# Hardware.net
KiCad netlist of a schematic drawn in EAGLE
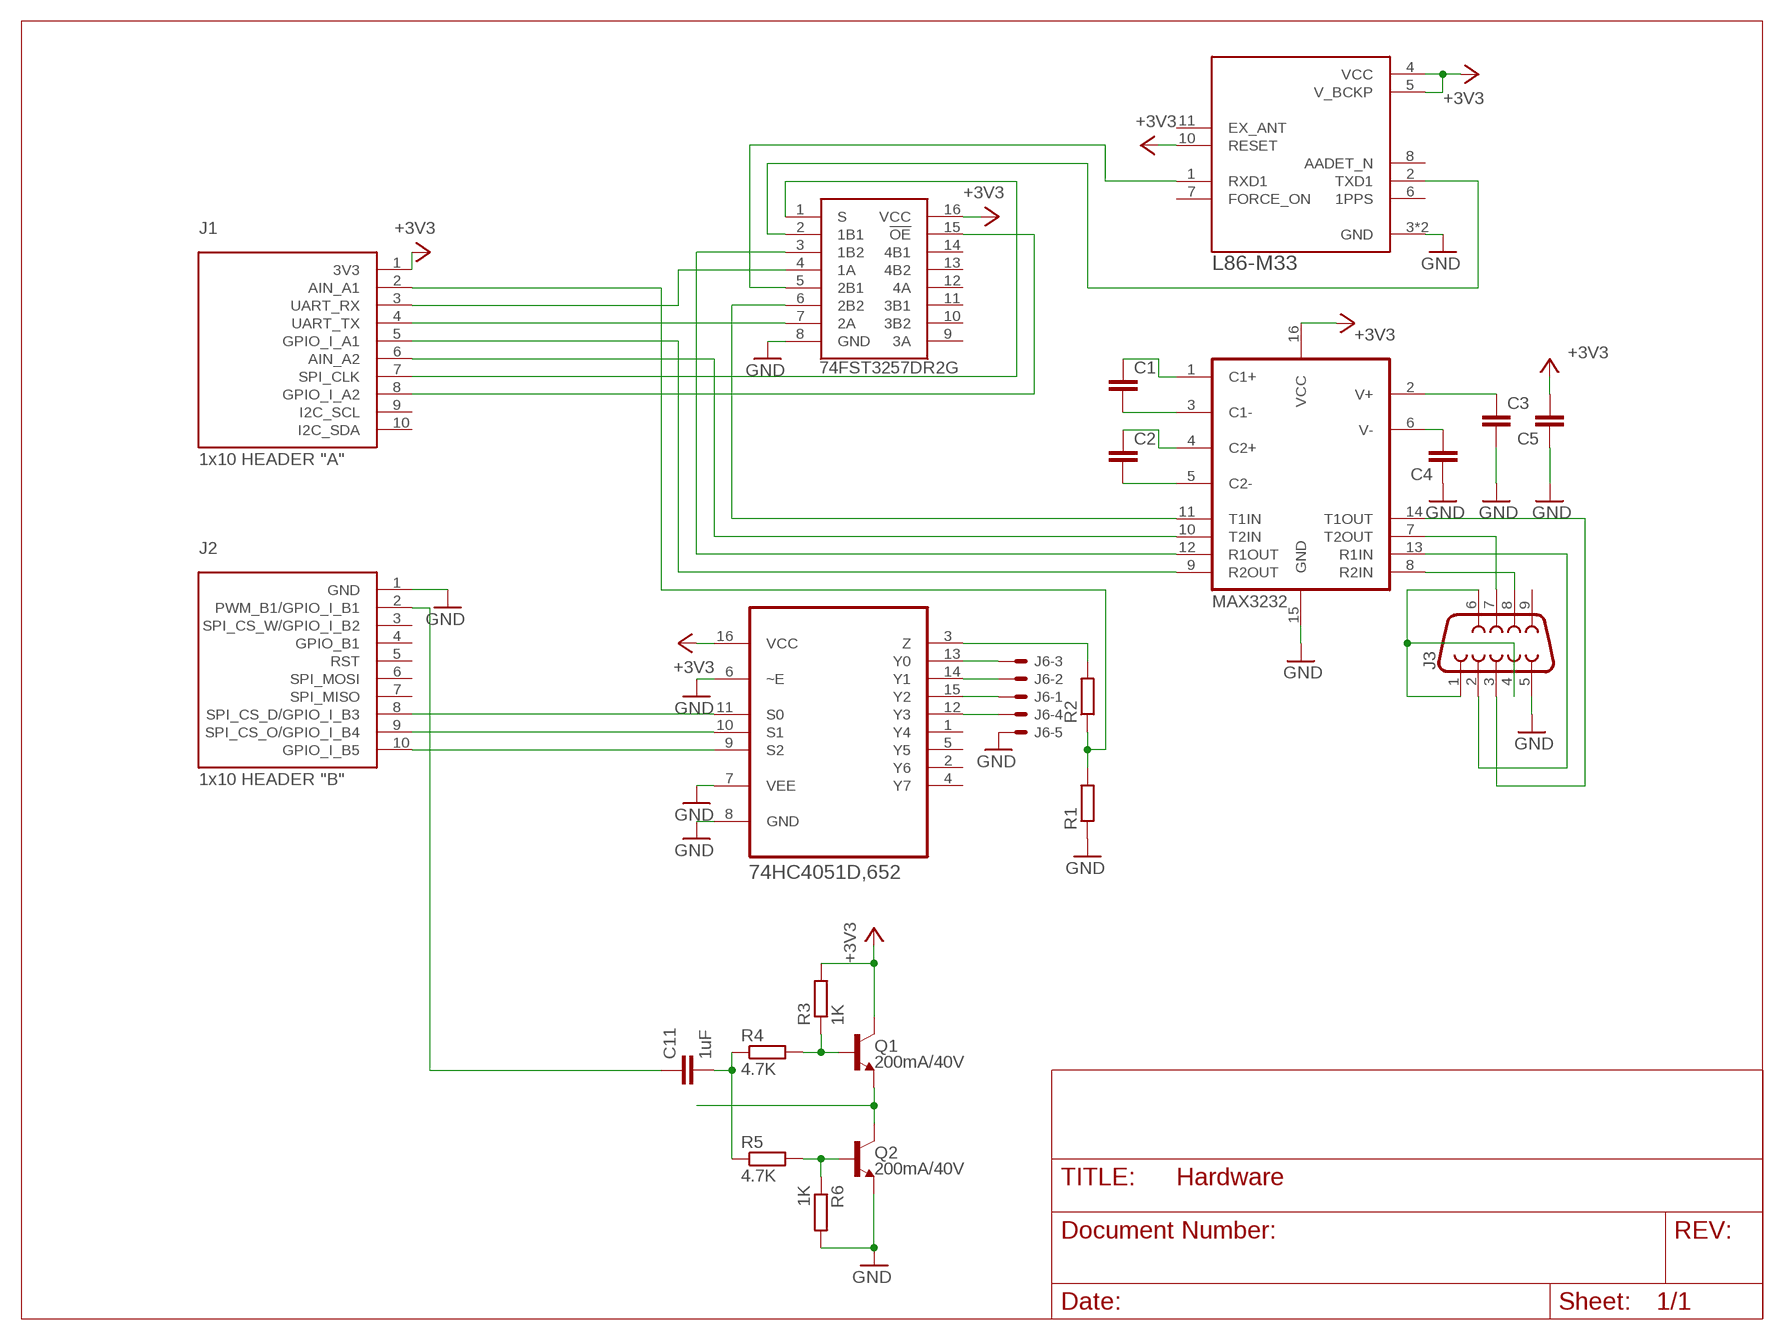
[diagram p0: schematic, sheet 1]

(export (version "E")
  (design (tool "Eeschema 10.0.6"))
  (components
    (comp (ref "C1")
      (value "C-EUC0805K")
      (footprint "eagle-import:C0805K")
      (libsource (lib "eagle-import") (part "C-EUC0805K"))
    )
    (comp (ref "C2")
      (value "C-EUC0805K")
      (footprint "eagle-import:C0805K")
      (libsource (lib "eagle-import") (part "C-EUC0805K"))
    )
    (comp (ref "C3")
      (value "C-EUC0805K")
      (footprint "eagle-import:C0805K")
      (libsource (lib "eagle-import") (part "C-EUC0805K"))
    )
    (comp (ref "C4")
      (value "C-EUC0805K")
      (footprint "eagle-import:C0805K")
      (libsource (lib "eagle-import") (part "C-EUC0805K"))
    )
    (comp (ref "C5")
      (value "C-EUC0805K")
      (footprint "eagle-import:C0805K")
      (libsource (lib "eagle-import") (part "C-EUC0805K"))
    )
    (comp (ref "C11")
      (value "1uF")
      (footprint "eagle-import:C025-024X044")
      (libsource (lib "eagle-import") (part "C-EU025-024X044"))
    )
    (comp (ref "IC1")
      (value "74FST3257DR2G")
      (footprint "eagle-import:SOIC127P600X175-16N")
      (fields (field (name "RS_PART_NUMBER") "8009395"))
      (libsource (lib "eagle-import") (part "74FST3257DR2G"))
    )
    (comp (ref "J1")
      (value "1x10 HEADER \"A\"")
      (footprint "eagle-import:1X10")
      (libsource (lib "eagle-import") (part "HEADER-1X10-J1"))
    )
    (comp (ref "J2")
      (value "1x10 HEADER \"B\"")
      (footprint "eagle-import:1X10")
      (libsource (lib "eagle-import") (part "HEADER-1X10-J2"))
    )
    (comp (ref "J3")
      (value "DB9MALE")
      (footprint "eagle-import:DB9_MALE")
      (libsource (lib "eagle-import") (part "DB9MALE"))
    )
    (comp (ref "J6")
      (value "22-27-2051-05")
      (footprint "eagle-import:6410-05")
      (fields (field (name "MF") "MOLEX"))
      (libsource (lib "eagle-import") (part "22-?-0527-2051"))
    )
    (comp (ref "Q1")
      (value "200mA/40V")
      (footprint "eagle-import:TO-92")
      (libsource (lib "eagle-import") (part "TRANS_NPN-2N3904"))
    )
    (comp (ref "Q2")
      (value "200mA/40V")
      (footprint "eagle-import:TO-92")
      (libsource (lib "eagle-import") (part "TRANS_NPN-2N3904"))
    )
    (comp (ref "R1")
      (value "R-EU_0207/7")
      (footprint "eagle-import:0207_7")
      (libsource (lib "eagle-import") (part "R-EU_0207/7"))
    )
    (comp (ref "R2")
      (value "R-EU_0207/7")
      (footprint "eagle-import:0207_7")
      (libsource (lib "eagle-import") (part "R-EU_0207/7"))
    )
    (comp (ref "R3")
      (value "1K")
      (footprint "eagle-import:0207_2V")
      (libsource (lib "eagle-import") (part "R-EU_0207/2V"))
    )
    (comp (ref "R4")
      (value "4.7K")
      (footprint "eagle-import:0207_2V")
      (libsource (lib "eagle-import") (part "R-EU_0207/2V"))
    )
    (comp (ref "R5")
      (value "4.7K")
      (footprint "eagle-import:0207_2V")
      (libsource (lib "eagle-import") (part "R-EU_0207/2V"))
    )
    (comp (ref "R6")
      (value "1K")
      (footprint "eagle-import:0207_2V")
      (libsource (lib "eagle-import") (part "R-EU_0207/2V"))
    )
    (comp (ref "U1")
      (value "MAX3232")
      (footprint "eagle-import:SO16")
      (libsource (lib "eagle-import") (part "MAX2323SOIC16"))
    )
    (comp (ref "U2")
      (value "L86-M33")
      (footprint "eagle-import:SON254P1840X1840X40-12N")
      (fields (field (name "MF") "Quectel"))
      (libsource (lib "eagle-import") (part "L86-M33"))
    )
    (comp (ref "U4")
      (value "74HC4051D,652")
      (footprint "eagle-import:SOIC127P600X175-16N")
      (fields (field (name "MF") "Nexperia"))
      (libsource (lib "eagle-import") (part "74HC4051D,652"))
    )
  )
  (nets
    (net (code "1") (name "+3V3") (class "Default")
      (node (ref "C5") (pin "2") (pinfunction "2_2") (pintype "passive"))
      (node (ref "IC1") (pin "16") (pinfunction "VCC_16") (pintype "input"))
      (node (ref "J1") (pin "1") (pinfunction "3V3_1") (pintype "bidirectional"))
      (node (ref "Q1") (pin "3") (pinfunction "C_3") (pintype "passive"))
      (node (ref "R3") (pin "2") (pinfunction "2_2") (pintype "passive"))
      (node (ref "U1") (pin "16") (pinfunction "VCC_16") (pintype "bidirectional"))
      (node (ref "U2") (pin "10") (pinfunction "RESET_10") (pintype "input"))
      (node (ref "U2") (pin "4") (pinfunction "VCC_4") (pintype "power_in"))
      (node (ref "U2") (pin "5") (pinfunction "V_BCKP_5") (pintype "power_in"))
      (node (ref "U4") (pin "16") (pinfunction "VCC_16") (pintype "power_in"))
    )
    (net (code "2") (name "GND") (class "Default")
      (node (ref "C3") (pin "2") (pinfunction "2_2") (pintype "passive"))
      (node (ref "C4") (pin "1") (pinfunction "1_1") (pintype "passive"))
      (node (ref "C5") (pin "1") (pinfunction "1_1") (pintype "passive"))
      (node (ref "IC1") (pin "8") (pinfunction "GND_8") (pintype "input"))
      (node (ref "J2") (pin "1") (pinfunction "GND_1") (pintype "bidirectional"))
      (node (ref "J3") (pin "5") (pinfunction "5_5") (pintype "passive"))
      (node (ref "J6") (pin "5") (pinfunction "S_5") (pintype "passive"))
      (node (ref "Q2") (pin "1") (pinfunction "E_1") (pintype "passive"))
      (node (ref "R1") (pin "1") (pinfunction "1_1") (pintype "passive"))
      (node (ref "R6") (pin "2") (pinfunction "2_2") (pintype "passive"))
      (node (ref "U1") (pin "15") (pinfunction "GND_15") (pintype "bidirectional"))
      (node (ref "U2") (pin "12") (pinfunction "GND_12") (pintype "passive"))
      (node (ref "U2") (pin "3") (pinfunction "GND_3") (pintype "passive"))
      (node (ref "U4") (pin "6") (pinfunction "~{E}_6") (pintype "input"))
      (node (ref "U4") (pin "7") (pinfunction "VEE_7") (pintype "power_in"))
      (node (ref "U4") (pin "8") (pinfunction "GND_8") (pintype "passive"))
    )
    (net (code "3") (name "Net-(C11-Pad2)") (class "Default")
      (node (ref "C11") (pin "2") (pinfunction "2_2") (pintype "passive"))
      (node (ref "R4") (pin "1") (pinfunction "1_1") (pintype "passive"))
      (node (ref "R5") (pin "1") (pinfunction "1_1") (pintype "passive"))
    )
    (net (code "4") (name "Net-(IC1-1A)") (class "Default")
      (node (ref "IC1") (pin "4") (pinfunction "1A_4") (pintype "input"))
      (node (ref "J1") (pin "3") (pinfunction "UART_RX_3") (pintype "bidirectional"))
    )
    (net (code "5") (name "Net-(IC1-1B1)") (class "Default")
      (node (ref "IC1") (pin "2") (pinfunction "1B1_2") (pintype "input"))
      (node (ref "U2") (pin "2") (pinfunction "TXD1_2") (pintype "output"))
    )
    (net (code "6") (name "Net-(IC1-1B2)") (class "Default")
      (node (ref "IC1") (pin "3") (pinfunction "1B2_3") (pintype "input"))
      (node (ref "U1") (pin "12") (pinfunction "R1OUT_12") (pintype "output"))
    )
    (net (code "7") (name "Net-(IC1-2A)") (class "Default")
      (node (ref "IC1") (pin "7") (pinfunction "2A_7") (pintype "input"))
      (node (ref "J1") (pin "4") (pinfunction "UART_TX_4") (pintype "bidirectional"))
    )
    (net (code "8") (name "Net-(IC1-2B1)") (class "Default")
      (node (ref "IC1") (pin "5") (pinfunction "2B1_5") (pintype "input"))
      (node (ref "U2") (pin "1") (pinfunction "RXD1_1") (pintype "input"))
    )
    (net (code "9") (name "Net-(IC1-2B2)") (class "Default")
      (node (ref "IC1") (pin "6") (pinfunction "2B2_6") (pintype "input"))
      (node (ref "U1") (pin "11") (pinfunction "T1IN_11") (pintype "input"))
    )
    (net (code "10") (name "Net-(IC1-S)") (class "Default")
      (node (ref "IC1") (pin "1") (pinfunction "S_1") (pintype "input"))
      (node (ref "J1") (pin "7") (pinfunction "SPI_CLK_7") (pintype "bidirectional"))
    )
    (net (code "11") (name "Net-(IC1-~{OE})") (class "Default")
      (node (ref "IC1") (pin "15") (pinfunction "~{OE}_15") (pintype "input"))
      (node (ref "J1") (pin "8") (pinfunction "GPIO_I_A2_8") (pintype "bidirectional"))
    )
    (net (code "12") (name "Net-(J1-AIN_A1)") (class "Default")
      (node (ref "J1") (pin "2") (pinfunction "AIN_A1_2") (pintype "bidirectional"))
      (node (ref "R1") (pin "2") (pinfunction "2_2") (pintype "passive"))
      (node (ref "R2") (pin "1") (pinfunction "1_1") (pintype "passive"))
    )
    (net (code "13") (name "Net-(J1-AIN_A2)") (class "Default")
      (node (ref "J1") (pin "6") (pinfunction "AIN_A2_6") (pintype "bidirectional"))
      (node (ref "U1") (pin "10") (pinfunction "T2IN_10") (pintype "input"))
    )
    (net (code "14") (name "Net-(J1-GPIO_I_A1)") (class "Default")
      (node (ref "J1") (pin "5") (pinfunction "GPIO_I_A1_5") (pintype "bidirectional"))
      (node (ref "U1") (pin "9") (pinfunction "R2OUT_9") (pintype "output"))
    )
    (net (code "15") (name "Net-(J2-GPIO_I_B5)") (class "Default")
      (node (ref "J2") (pin "10") (pinfunction "GPIO_I_B5_10") (pintype "bidirectional"))
      (node (ref "U4") (pin "9") (pinfunction "S2_9") (pintype "input"))
    )
    (net (code "16") (name "Net-(J2-PWM_B1{slash}GPIO_I_B1)") (class "Default")
      (node (ref "C11") (pin "1") (pinfunction "1_1") (pintype "passive"))
      (node (ref "J2") (pin "2") (pinfunction "PWM_B1/GPIO_I_B1_2") (pintype "bidirectional"))
    )
    (net (code "17") (name "Net-(J2-SPI_CS_D{slash}GPIO_I_B3)") (class "Default")
      (node (ref "J2") (pin "8") (pinfunction "SPI_CS_D/GPIO_I_B3_8") (pintype "bidirectional"))
      (node (ref "U4") (pin "11") (pinfunction "S0_11") (pintype "input"))
    )
    (net (code "18") (name "Net-(J2-SPI_CS_O{slash}GPIO_I_B4)") (class "Default")
      (node (ref "J2") (pin "9") (pinfunction "SPI_CS_O/GPIO_I_B4_9") (pintype "bidirectional"))
      (node (ref "U4") (pin "10") (pinfunction "S1_10") (pintype "input"))
    )
    (net (code "19") (name "Net-(J3-Pad1)") (class "Default")
      (node (ref "J3") (pin "1") (pinfunction "1_1") (pintype "passive"))
      (node (ref "J3") (pin "4") (pinfunction "4_4") (pintype "passive"))
      (node (ref "J3") (pin "6") (pinfunction "6_6") (pintype "passive"))
    )
    (net (code "20") (name "Net-(J6A-S)") (class "Default")
      (node (ref "J6") (pin "1") (pinfunction "S_1") (pintype "passive"))
      (node (ref "U4") (pin "15") (pinfunction "Y2_15") (pintype "bidirectional"))
    )
    (net (code "21") (name "Net-(J6B-S)") (class "Default")
      (node (ref "J6") (pin "2") (pinfunction "S_2") (pintype "passive"))
      (node (ref "U4") (pin "14") (pinfunction "Y1_14") (pintype "bidirectional"))
    )
    (net (code "22") (name "Net-(J6C-S)") (class "Default")
      (node (ref "J6") (pin "3") (pinfunction "S_3") (pintype "passive"))
      (node (ref "U4") (pin "13") (pinfunction "Y0_13") (pintype "bidirectional"))
    )
    (net (code "23") (name "Net-(J6D-S)") (class "Default")
      (node (ref "J6") (pin "4") (pinfunction "S_4") (pintype "passive"))
      (node (ref "U4") (pin "12") (pinfunction "Y3_12") (pintype "bidirectional"))
    )
    (net (code "24") (name "Net-(Q1-B)") (class "Default")
      (node (ref "Q1") (pin "2") (pinfunction "B_2") (pintype "passive"))
      (node (ref "R3") (pin "1") (pinfunction "1_1") (pintype "passive"))
      (node (ref "R4") (pin "2") (pinfunction "2_2") (pintype "passive"))
    )
    (net (code "25") (name "Net-(Q1-E)") (class "Default")
      (node (ref "Q1") (pin "1") (pinfunction "E_1") (pintype "passive"))
      (node (ref "Q2") (pin "3") (pinfunction "C_3") (pintype "passive"))
    )
    (net (code "26") (name "Net-(Q2-B)") (class "Default")
      (node (ref "Q2") (pin "2") (pinfunction "B_2") (pintype "passive"))
      (node (ref "R5") (pin "2") (pinfunction "2_2") (pintype "passive"))
      (node (ref "R6") (pin "1") (pinfunction "1_1") (pintype "passive"))
    )
    (net (code "27") (name "Net-(U1-C1+)") (class "Default")
      (node (ref "C1") (pin "1") (pinfunction "1_1") (pintype "passive"))
      (node (ref "U1") (pin "1") (pinfunction "C1+_1") (pintype "bidirectional"))
    )
    (net (code "28") (name "Net-(U1-C1-)") (class "Default")
      (node (ref "C1") (pin "2") (pinfunction "2_2") (pintype "passive"))
      (node (ref "U1") (pin "3") (pinfunction "C1-_3") (pintype "bidirectional"))
    )
    (net (code "29") (name "Net-(U1-C2+)") (class "Default")
      (node (ref "C2") (pin "1") (pinfunction "1_1") (pintype "passive"))
      (node (ref "U1") (pin "4") (pinfunction "C2+_4") (pintype "bidirectional"))
    )
    (net (code "30") (name "Net-(U1-C2-)") (class "Default")
      (node (ref "C2") (pin "2") (pinfunction "2_2") (pintype "passive"))
      (node (ref "U1") (pin "5") (pinfunction "C2-_5") (pintype "bidirectional"))
    )
    (net (code "31") (name "Net-(U1-R1IN)") (class "Default")
      (node (ref "J3") (pin "2") (pinfunction "2_2") (pintype "passive"))
      (node (ref "U1") (pin "13") (pinfunction "R1IN_13") (pintype "input"))
    )
    (net (code "32") (name "Net-(U1-R2IN)") (class "Default")
      (node (ref "J3") (pin "8") (pinfunction "8_8") (pintype "passive"))
      (node (ref "U1") (pin "8") (pinfunction "R2IN_8") (pintype "input"))
    )
    (net (code "33") (name "Net-(U1-T1OUT)") (class "Default")
      (node (ref "J3") (pin "3") (pinfunction "3_3") (pintype "passive"))
      (node (ref "U1") (pin "14") (pinfunction "T1OUT_14") (pintype "output"))
    )
    (net (code "34") (name "Net-(U1-T2OUT)") (class "Default")
      (node (ref "J3") (pin "7") (pinfunction "7_7") (pintype "passive"))
      (node (ref "U1") (pin "7") (pinfunction "T2OUT_7") (pintype "output"))
    )
    (net (code "35") (name "Net-(U1-V+)") (class "Default")
      (node (ref "C3") (pin "1") (pinfunction "1_1") (pintype "passive"))
      (node (ref "U1") (pin "2") (pinfunction "V+_2") (pintype "bidirectional"))
    )
    (net (code "36") (name "Net-(U1-V-)") (class "Default")
      (node (ref "C4") (pin "2") (pinfunction "2_2") (pintype "passive"))
      (node (ref "U1") (pin "6") (pinfunction "V-_6") (pintype "bidirectional"))
    )
    (net (code "37") (name "Net-(U4-Z)") (class "Default")
      (node (ref "R2") (pin "2") (pinfunction "2_2") (pintype "passive"))
      (node (ref "U4") (pin "3") (pinfunction "Z_3") (pintype "bidirectional"))
    )
    (net (code "38") (name "unconnected-(IC1-3A-Pad9)") (class "Default")
      (node (ref "IC1") (pin "9") (pinfunction "3A_9") (pintype "input"))
    )
    (net (code "39") (name "unconnected-(IC1-3B1-Pad11)") (class "Default")
      (node (ref "IC1") (pin "11") (pinfunction "3B1_11") (pintype "input"))
    )
    (net (code "40") (name "unconnected-(IC1-3B2-Pad10)") (class "Default")
      (node (ref "IC1") (pin "10") (pinfunction "3B2_10") (pintype "input"))
    )
    (net (code "41") (name "unconnected-(IC1-4A-Pad12)") (class "Default")
      (node (ref "IC1") (pin "12") (pinfunction "4A_12") (pintype "input"))
    )
    (net (code "42") (name "unconnected-(IC1-4B1-Pad14)") (class "Default")
      (node (ref "IC1") (pin "14") (pinfunction "4B1_14") (pintype "input"))
    )
    (net (code "43") (name "unconnected-(IC1-4B2-Pad13)") (class "Default")
      (node (ref "IC1") (pin "13") (pinfunction "4B2_13") (pintype "input"))
    )
    (net (code "44") (name "unconnected-(J1-I2C_SCL-Pad9)") (class "Default")
      (node (ref "J1") (pin "9") (pinfunction "I2C_SCL_9") (pintype "bidirectional"))
    )
    (net (code "45") (name "unconnected-(J1-I2C_SDA-Pad10)") (class "Default")
      (node (ref "J1") (pin "10") (pinfunction "I2C_SDA_10") (pintype "bidirectional"))
    )
    (net (code "46") (name "unconnected-(J2-GPIO_B1-Pad4)") (class "Default")
      (node (ref "J2") (pin "4") (pinfunction "GPIO_B1_4") (pintype "bidirectional"))
    )
    (net (code "47") (name "unconnected-(J2-RST-Pad5)") (class "Default")
      (node (ref "J2") (pin "5") (pinfunction "RST_5") (pintype "bidirectional"))
    )
    (net (code "48") (name "unconnected-(J2-SPI_CS_W{slash}GPIO_I_B2-Pad3)") (class "Default")
      (node (ref "J2") (pin "3") (pinfunction "SPI_CS_W/GPIO_I_B2_3") (pintype "bidirectional"))
    )
    (net (code "49") (name "unconnected-(J2-SPI_MISO-Pad7)") (class "Default")
      (node (ref "J2") (pin "7") (pinfunction "SPI_MISO_7") (pintype "bidirectional"))
    )
    (net (code "50") (name "unconnected-(J2-SPI_MOSI-Pad6)") (class "Default")
      (node (ref "J2") (pin "6") (pinfunction "SPI_MOSI_6") (pintype "bidirectional"))
    )
    (net (code "51") (name "unconnected-(J3-Pad9)") (class "Default")
      (node (ref "J3") (pin "9") (pinfunction "9_9") (pintype "passive"))
    )
    (net (code "52") (name "unconnected-(U2-1PPS-Pad6)") (class "Default")
      (node (ref "U2") (pin "6") (pinfunction "1PPS_6") (pintype "output"))
    )
    (net (code "53") (name "unconnected-(U2-AADET_N-Pad8)") (class "Default")
      (node (ref "U2") (pin "8") (pinfunction "AADET_N_8") (pintype "output"))
    )
    (net (code "54") (name "unconnected-(U2-EX_ANT-Pad11)") (class "Default")
      (node (ref "U2") (pin "11") (pinfunction "EX_ANT_11") (pintype "input"))
    )
    (net (code "55") (name "unconnected-(U2-FORCE_ON-Pad7)") (class "Default")
      (node (ref "U2") (pin "7") (pinfunction "FORCE_ON_7") (pintype "input"))
    )
    (net (code "56") (name "unconnected-(U4-Y4-Pad1)") (class "Default")
      (node (ref "U4") (pin "1") (pinfunction "Y4_1") (pintype "bidirectional"))
    )
    (net (code "57") (name "unconnected-(U4-Y5-Pad5)") (class "Default")
      (node (ref "U4") (pin "5") (pinfunction "Y5_5") (pintype "bidirectional"))
    )
    (net (code "58") (name "unconnected-(U4-Y6-Pad2)") (class "Default")
      (node (ref "U4") (pin "2") (pinfunction "Y6_2") (pintype "bidirectional"))
    )
    (net (code "59") (name "unconnected-(U4-Y7-Pad4)") (class "Default")
      (node (ref "U4") (pin "4") (pinfunction "Y7_4") (pintype "bidirectional"))
    )
  )
)
